# LNA.net
KiCad netlist of a schematic drawn in Altium Designer
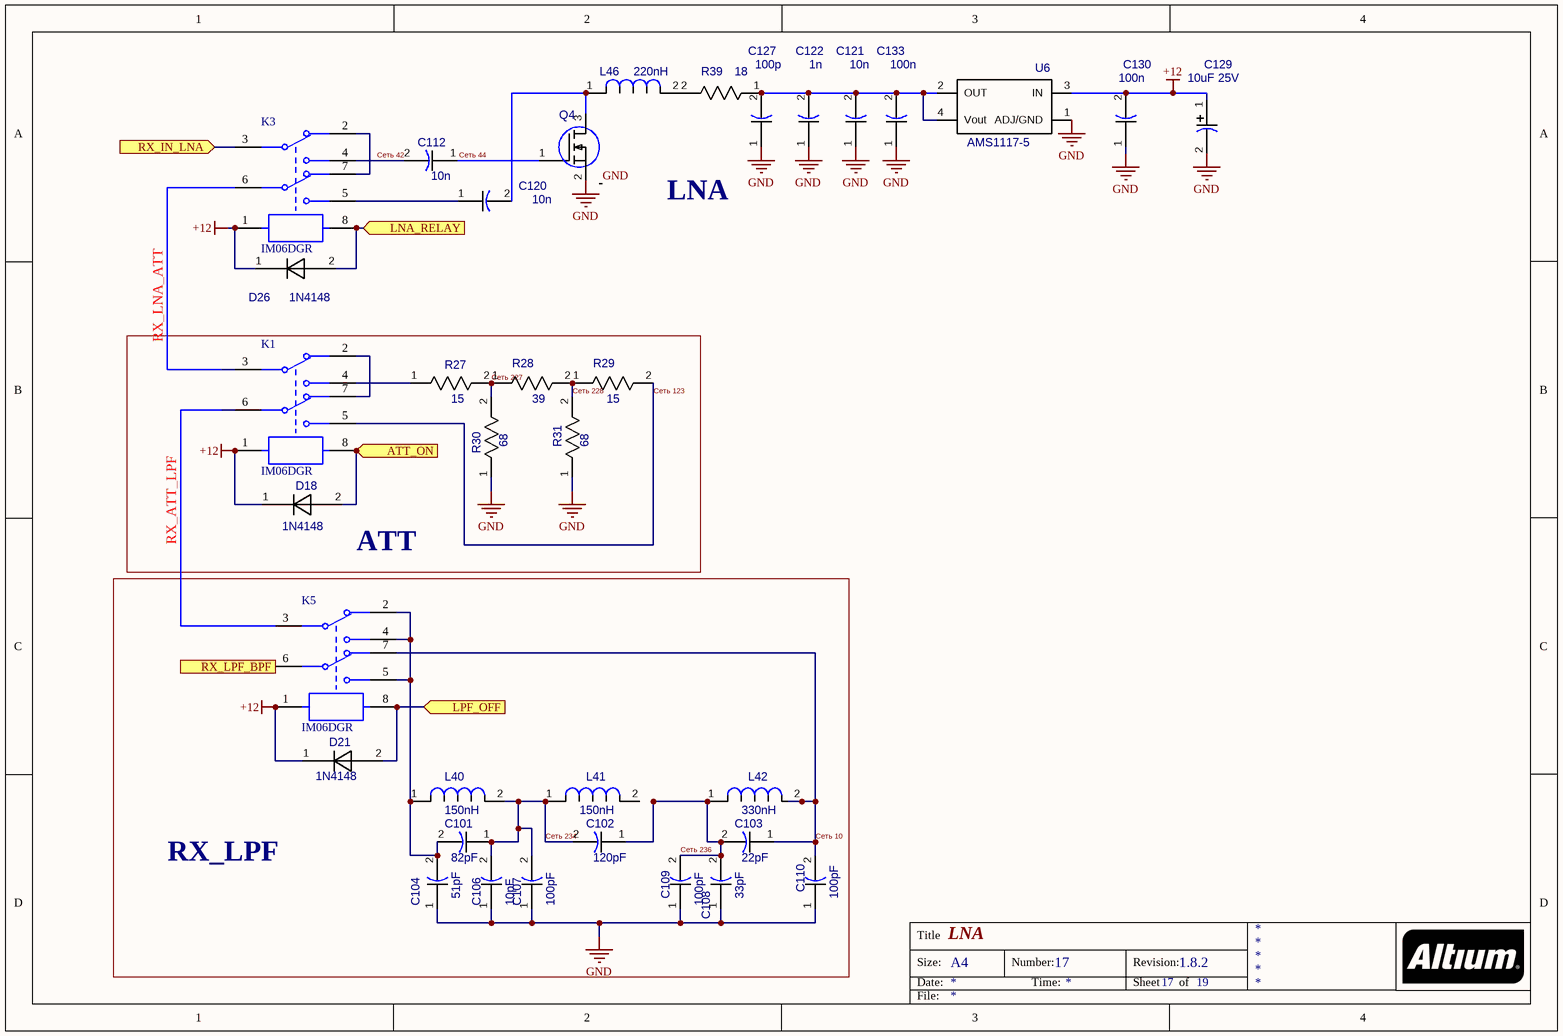
[diagram p0: LNA.SchDoc]

(export (version "E")
  (design (tool "Eeschema 10.0.6"))
  (components
    (comp (ref "C101")
      (value "82pF")
      (footprint "CAP_0805")
      (description "CAP_0805")
      (libsource (lib "*") (part "CAP_0805"))
    )
    (comp (ref "C102")
      (value "120pF")
      (footprint "CAP_0805")
      (description "CAP_0805")
      (libsource (lib "*") (part "CAP_0805"))
    )
    (comp (ref "C103")
      (value "22pF")
      (footprint "CAP_0805")
      (description "CAP_0805")
      (libsource (lib "*") (part "CAP_0805"))
    )
    (comp (ref "C104")
      (value "51pF")
      (footprint "CAP_0805")
      (description "CAP_0805")
      (libsource (lib "*") (part "CAP_0805"))
    )
    (comp (ref "C106")
      (value "10pF")
      (footprint "CAP_0805")
      (description "CAP_0805")
      (libsource (lib "*") (part "CAP_0805"))
    )
    (comp (ref "C107")
      (value "100pF")
      (footprint "CAP_0805")
      (description "CAP_0805")
      (libsource (lib "*") (part "CAP_0805"))
    )
    (comp (ref "C108")
      (value "33pF")
      (footprint "CAP_0805")
      (description "CAP_0805")
      (libsource (lib "*") (part "CAP_0805"))
    )
    (comp (ref "C109")
      (value "100pF")
      (footprint "CAP_0805")
      (description "CAP_0805")
      (libsource (lib "*") (part "CAP_0805"))
    )
    (comp (ref "C110")
      (value "100pF")
      (footprint "CAP_0805")
      (description "CAP_0805")
      (libsource (lib "*") (part "CAP_0805"))
    )
    (comp (ref "C112")
      (value "10n")
      (footprint "CAP_0805")
      (description "CAP_0805")
      (libsource (lib "*") (part "CAP_0805"))
    )
    (comp (ref "C120")
      (value "10n")
      (footprint "CAP_0805")
      (description "CAP_0805")
      (libsource (lib "*") (part "CAP_0805"))
    )
    (comp (ref "C121")
      (value "10n")
      (footprint "6-0805_M")
      (description "CAP_0805")
      (libsource (lib "*") (part "CAP_0805"))
    )
    (comp (ref "C122")
      (value "1n")
      (footprint "6-0805_M")
      (description "CAP_0805")
      (libsource (lib "*") (part "CAP_0805"))
    )
    (comp (ref "C127")
      (value "100p")
      (footprint "6-0805_M")
      (description "CAP_0805")
      (libsource (lib "*") (part "CAP_0805"))
    )
    (comp (ref "C129")
      (value "10uF 25V")
      (footprint "CAPAE_5.3x5.3h6.1")
      (description "CAPAE_5.3x5.3h6.1")
      (libsource (lib "*") (part "CAPAE_5.3x5.3h6.1"))
    )
    (comp (ref "C130")
      (value "100n")
      (footprint "CAP_0805")
      (description "CAP_0805")
      (libsource (lib "") (part "CAP_0805_1"))
    )
    (comp (ref "C133")
      (value "100n")
      (footprint "CAP_0805")
      (description "CAP_0805")
      (libsource (lib "*") (part "CAP_0805"))
    )
    (comp (ref "D18") (value "1N4148") (footprint "1N4148") (libsource (lib "*") (part "1N4148")))
    (comp (ref "D21") (value "1N4148") (footprint "1N4148") (libsource (lib "*") (part "1N4148")))
    (comp (ref "D26") (value "1N4148") (footprint "1N4148") (libsource (lib "*") (part "1N4148")))
    (comp (ref "K1")
      (value "IM06DGR")
      (footprint "TECO-SMT-8_V")
      (description "Signal Relay, 5 A, 12 VDC, -40 to 85 degC, 8-Pin SMD, RoHS, Tape and Reel")
      (fields
        (field (name "MANUFACTURER") "TE Connectivity")
        (field (name "APPROVAL CATEGORY") "ULRecognised")
        (field (name "APPROVAL BODIES") "EN/IEC")
      )
      (libsource (lib "Altium Content Vault") (part "RELAY-DPDT-8_C"))
    )
    (comp (ref "K3")
      (value "IM06DGR")
      (footprint "TECO-SMT-8_V")
      (description "Signal Relay, 5 A, 12 VDC, -40 to 85 degC, 8-Pin SMD, RoHS, Tape and Reel")
      (fields
        (field (name "MANUFACTURER") "TE Connectivity")
        (field (name "APPROVAL CATEGORY") "ULRecognised")
        (field (name "APPROVAL BODIES") "EN/IEC")
      )
      (libsource (lib "Altium Content Vault") (part "RELAY-DPDT-8_C"))
    )
    (comp (ref "K5")
      (value "IM06DGR")
      (footprint "TECO-SMT-8_V")
      (description "Signal Relay, 5 A, 12 VDC, -40 to 85 degC, 8-Pin SMD, RoHS, Tape and Reel")
      (fields
        (field (name "MANUFACTURER") "TE Connectivity")
        (field (name "APPROVAL CATEGORY") "ULRecognised")
        (field (name "APPROVAL BODIES") "EN/IEC")
      )
      (libsource (lib "Altium Content Vault") (part "RELAY-DPDT-8_C"))
    )
    (comp (ref "L40")
      (value "150nH")
      (footprint "IND_0805")
      (description "IND_0805")
      (libsource (lib "*") (part "IND_0805"))
    )
    (comp (ref "L41")
      (value "150nH")
      (footprint "IND_0805")
      (description "IND_0805")
      (libsource (lib "*") (part "IND_0805"))
    )
    (comp (ref "L42")
      (value "330nH")
      (footprint "IND_0805")
      (description "IND_0805")
      (libsource (lib "*") (part "IND_0805"))
    )
    (comp (ref "L46")
      (value "220nH")
      (footprint "IND_1206")
      (description "IND_1206")
      (libsource (lib "*") (part "IND_1206"))
    )
    (comp (ref "Q4")
      (value "PGA-103+")
      (footprint "SOT89")
      (description "MOSFET")
      (libsource (lib "*") (part "PGA-103+"))
    )
    (comp (ref "R27")
      (value "15")
      (footprint "RES_0805")
      (description "RES_0805")
      (libsource (lib "*") (part "RES_0805"))
    )
    (comp (ref "R28")
      (value "39")
      (footprint "RES_0805")
      (description "RES_0805")
      (libsource (lib "*") (part "RES_0805"))
    )
    (comp (ref "R29")
      (value "15")
      (footprint "RES_0805")
      (description "RES_0805")
      (libsource (lib "*") (part "RES_0805"))
    )
    (comp (ref "R30")
      (value "68")
      (footprint "RES_0805")
      (description "RES_0805")
      (libsource (lib "*") (part "RES_0805"))
    )
    (comp (ref "R31")
      (value "68")
      (footprint "RES_0805")
      (description "RES_0805")
      (libsource (lib "*") (part "RES_0805"))
    )
    (comp (ref "R39")
      (value "18")
      (footprint "RES_1206")
      (description "RES_1206")
      (libsource (lib "*") (part "RES_1206"))
    )
    (comp (ref "U6") (value "AMS1117-5") (footprint "AMS1117-5") (libsource (lib "*") (part "AMS1117-5")))
  )
  (nets
    (net (code "1") (name "+12") (class "Default")
      (node (ref "C129") (pin "1") (pinfunction "PLUS_1") (pintype "passive"))
      (node (ref "C130") (pin "2") (pinfunction "2_2") (pintype "passive"))
      (node (ref "D18") (pin "1") (pinfunction "K_1") (pintype "passive"))
      (node (ref "D21") (pin "1") (pinfunction "K_1") (pintype "passive"))
      (node (ref "D26") (pin "1") (pinfunction "K_1") (pintype "passive"))
      (node (ref "K1") (pin "1") (pinfunction "1_1") (pintype "passive"))
      (node (ref "K3") (pin "1") (pinfunction "1_1") (pintype "passive"))
      (node (ref "K5") (pin "1") (pinfunction "1_1") (pintype "passive"))
      (node (ref "U6") (pin "3") (pinfunction "IN_3") (pintype "passive"))
    )
    (net (code "2") (name "/ATT_ON") (class "Default")
      (node (ref "D18") (pin "2") (pinfunction "A_2") (pintype "passive"))
      (node (ref "K1") (pin "8") (pinfunction "8_8") (pintype "passive"))
    )
    (net (code "3") (name "/LNA_RELAY") (class "Default")
      (node (ref "D26") (pin "2") (pinfunction "A_2") (pintype "passive"))
      (node (ref "K3") (pin "8") (pinfunction "8_8") (pintype "passive"))
    )
    (net (code "4") (name "/LPF_OFF") (class "Default")
      (node (ref "D21") (pin "2") (pinfunction "A_2") (pintype "passive"))
      (node (ref "K5") (pin "8") (pinfunction "8_8") (pintype "passive"))
    )
    (net (code "5") (name "/RX_IN_LNA") (class "Default")
      (node (ref "K3") (pin "3") (pinfunction "3_3") (pintype "passive"))
    )
    (net (code "6") (name "/RX_LPF_BPF") (class "Default")
      (node (ref "K5") (pin "6") (pinfunction "6_6") (pintype "passive"))
    )
    (net (code "7") (name "/Сеть 10") (class "Default")
      (node (ref "C103") (pin "1") (pinfunction "1_1") (pintype "passive"))
      (node (ref "C110") (pin "2") (pinfunction "2_2") (pintype "passive"))
      (node (ref "K5") (pin "7") (pinfunction "7_7") (pintype "passive"))
      (node (ref "L42") (pin "2") (pinfunction "2_2") (pintype "passive"))
    )
    (net (code "8") (name "/Сеть 42") (class "Default")
      (node (ref "C112") (pin "2") (pinfunction "2_2") (pintype "passive"))
      (node (ref "K3") (pin "4") (pinfunction "4_4") (pintype "passive"))
    )
    (net (code "9") (name "/Сеть 44") (class "Default")
      (node (ref "C112") (pin "1") (pinfunction "1_1") (pintype "passive"))
      (node (ref "Q4") (pin "1") (pinfunction "G_1") (pintype "passive"))
    )
    (net (code "10") (name "/Сеть 123") (class "Default")
      (node (ref "K1") (pin "5") (pinfunction "5_5") (pintype "passive"))
      (node (ref "R29") (pin "2") (pinfunction "2_2") (pintype "passive"))
    )
    (net (code "11") (name "/Сеть 227") (class "Default")
      (node (ref "R27") (pin "2") (pinfunction "2_2") (pintype "passive"))
      (node (ref "R28") (pin "1") (pinfunction "1_1") (pintype "passive"))
      (node (ref "R30") (pin "2") (pinfunction "2_2") (pintype "passive"))
    )
    (net (code "12") (name "/Сеть 228") (class "Default")
      (node (ref "R28") (pin "2") (pinfunction "2_2") (pintype "passive"))
      (node (ref "R29") (pin "1") (pinfunction "1_1") (pintype "passive"))
      (node (ref "R31") (pin "2") (pinfunction "2_2") (pintype "passive"))
    )
    (net (code "13") (name "/Сеть 234") (class "Default")
      (node (ref "C101") (pin "1") (pinfunction "1_1") (pintype "passive"))
      (node (ref "C102") (pin "2") (pinfunction "2_2") (pintype "passive"))
      (node (ref "C106") (pin "2") (pinfunction "2_2") (pintype "passive"))
      (node (ref "C107") (pin "2") (pinfunction "2_2") (pintype "passive"))
      (node (ref "L40") (pin "2") (pinfunction "2_2") (pintype "passive"))
      (node (ref "L41") (pin "1") (pinfunction "1_1") (pintype "passive"))
    )
    (net (code "14") (name "/Сеть 236") (class "Default")
      (node (ref "C102") (pin "1") (pinfunction "1_1") (pintype "passive"))
      (node (ref "C103") (pin "2") (pinfunction "2_2") (pintype "passive"))
      (node (ref "C108") (pin "2") (pinfunction "2_2") (pintype "passive"))
      (node (ref "C109") (pin "2") (pinfunction "2_2") (pintype "passive"))
      (node (ref "L42") (pin "1") (pinfunction "1_1") (pintype "passive"))
    )
    (net (code "15") (name "GND") (class "Default")
      (node (ref "C104") (pin "1") (pinfunction "1_1") (pintype "passive"))
      (node (ref "C106") (pin "1") (pinfunction "1_1") (pintype "passive"))
      (node (ref "C107") (pin "1") (pinfunction "1_1") (pintype "passive"))
      (node (ref "C108") (pin "1") (pinfunction "1_1") (pintype "passive"))
      (node (ref "C109") (pin "1") (pinfunction "1_1") (pintype "passive"))
      (node (ref "C110") (pin "1") (pinfunction "1_1") (pintype "passive"))
      (node (ref "C121") (pin "1") (pinfunction "1_1") (pintype "passive"))
      (node (ref "C122") (pin "1") (pinfunction "1_1") (pintype "passive"))
      (node (ref "C127") (pin "1") (pinfunction "1_1") (pintype "passive"))
      (node (ref "C129") (pin "2") (pinfunction "MINUS_2") (pintype "passive"))
      (node (ref "C130") (pin "1") (pinfunction "1_1") (pintype "passive"))
      (node (ref "C133") (pin "1") (pinfunction "1_1") (pintype "passive"))
      (node (ref "Q4") (pin "0") (pinfunction "0_0") (pintype "passive"))
      (node (ref "Q4") (pin "2") (pinfunction "S_2") (pintype "passive"))
      (node (ref "R30") (pin "1") (pinfunction "1_1") (pintype "passive"))
      (node (ref "R31") (pin "1") (pinfunction "1_1") (pintype "passive"))
      (node (ref "U6") (pin "1") (pinfunction "ADJ/GND_1") (pintype "passive"))
    )
    (net (code "16") (name "Net-(C101-Pad2)") (class "Default")
      (node (ref "C101") (pin "2") (pinfunction "2_2") (pintype "passive"))
      (node (ref "C104") (pin "2") (pinfunction "2_2") (pintype "passive"))
      (node (ref "K5") (pin "2") (pinfunction "2_2") (pintype "passive"))
      (node (ref "K5") (pin "4") (pinfunction "4_4") (pintype "passive"))
      (node (ref "K5") (pin "5") (pinfunction "5_5") (pintype "passive"))
      (node (ref "L40") (pin "1") (pinfunction "1_1") (pintype "passive"))
    )
    (net (code "17") (name "Net-(C120-Pad1)") (class "Default")
      (node (ref "C120") (pin "1") (pinfunction "1_1") (pintype "passive"))
      (node (ref "K3") (pin "5") (pinfunction "5_5") (pintype "passive"))
    )
    (net (code "18") (name "Net-(K1-Pad2)") (class "Default")
      (node (ref "K1") (pin "2") (pinfunction "2_2") (pintype "passive"))
      (node (ref "K1") (pin "7") (pinfunction "7_7") (pintype "passive"))
    )
    (net (code "19") (name "Net-(K1-Pad3)") (class "Default")
      (node (ref "K1") (pin "3") (pinfunction "3_3") (pintype "passive"))
      (node (ref "K3") (pin "6") (pinfunction "6_6") (pintype "passive"))
    )
    (net (code "20") (name "Net-(K1-Pad4)") (class "Default")
      (node (ref "K1") (pin "4") (pinfunction "4_4") (pintype "passive"))
      (node (ref "R27") (pin "1") (pinfunction "1_1") (pintype "passive"))
    )
    (net (code "21") (name "Net-(K1-Pad6)") (class "Default")
      (node (ref "K1") (pin "6") (pinfunction "6_6") (pintype "passive"))
      (node (ref "K5") (pin "3") (pinfunction "3_3") (pintype "passive"))
    )
    (net (code "22") (name "Net-(K3-Pad2)") (class "Default")
      (node (ref "K3") (pin "2") (pinfunction "2_2") (pintype "passive"))
      (node (ref "K3") (pin "7") (pinfunction "7_7") (pintype "passive"))
    )
    (net (code "23") (name "Net-(L46-Pad2)") (class "Default")
      (node (ref "L46") (pin "2") (pinfunction "2_2") (pintype "passive"))
      (node (ref "R39") (pin "2") (pinfunction "2_2") (pintype "passive"))
    )
    (net (code "24") (name "Net-(Q4-D)") (class "Default")
      (node (ref "C120") (pin "2") (pinfunction "2_2") (pintype "passive"))
      (node (ref "L46") (pin "1") (pinfunction "1_1") (pintype "passive"))
      (node (ref "Q4") (pin "3") (pinfunction "D_3") (pintype "passive"))
    )
    (net (code "25") (name "Net-(U6-OUT)") (class "Default")
      (node (ref "C121") (pin "2") (pinfunction "2_2") (pintype "passive"))
      (node (ref "C122") (pin "2") (pinfunction "2_2") (pintype "passive"))
      (node (ref "C127") (pin "2") (pinfunction "2_2") (pintype "passive"))
      (node (ref "C133") (pin "2") (pinfunction "2_2") (pintype "passive"))
      (node (ref "R39") (pin "1") (pinfunction "1_1") (pintype "passive"))
      (node (ref "U6") (pin "2") (pinfunction "OUT_2") (pintype "passive"))
      (node (ref "U6") (pin "4") (pinfunction "Vout_4") (pintype "passive"))
    )
    (net (code "26") (name "unconnected-(L41-Pad2)") (class "Default")
      (node (ref "L41") (pin "2") (pinfunction "2_2") (pintype "passive"))
    )
  )
)
